# ADC.net
KiCad netlist of a schematic drawn in EAGLE
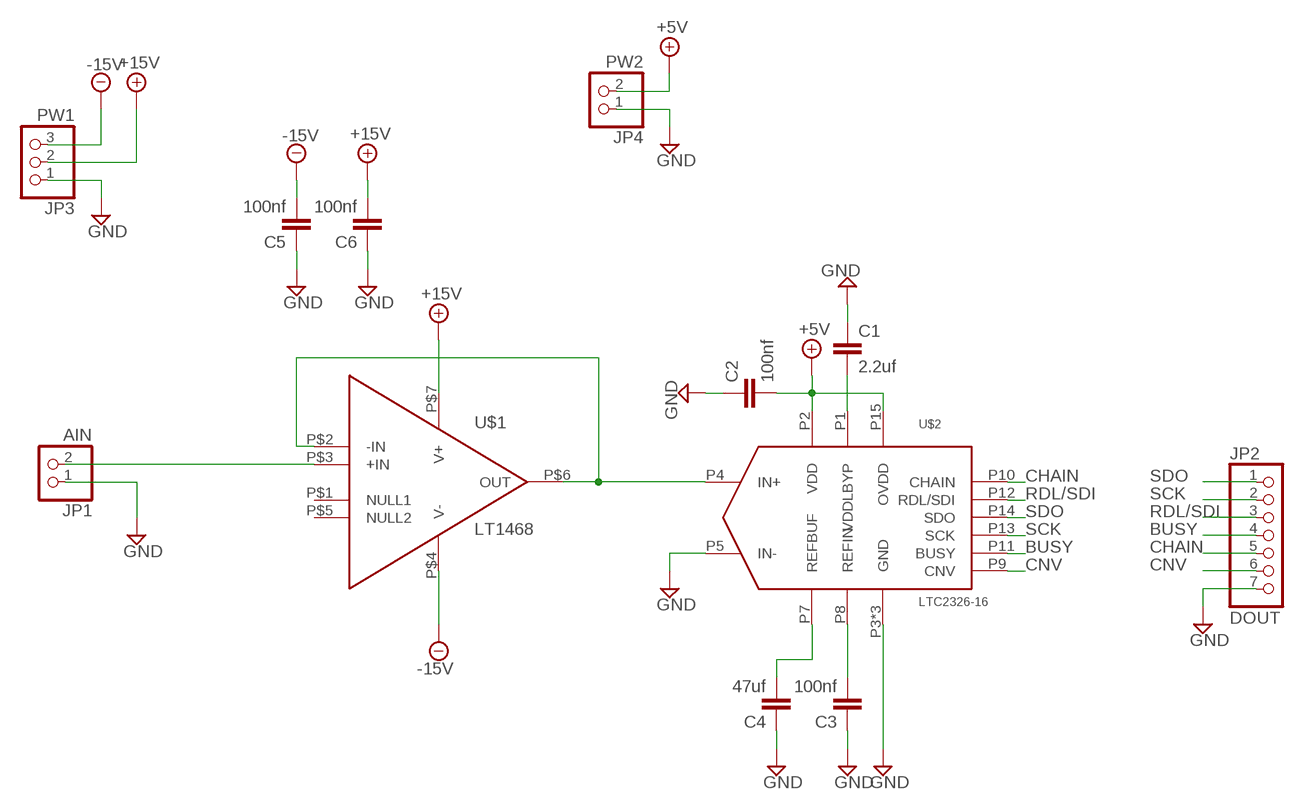
[diagram p0: schematic, sheet 1]

(export (version "E")
  (design (tool "Eeschema 10.0.6"))
  (components
    (comp (ref "C1")
      (value "2.2uf")
      (footprint "eagle-import:C0603")
      (libsource (lib "eagle-import") (part "C-EUC0603"))
    )
    (comp (ref "C2")
      (value "100nf")
      (footprint "eagle-import:C0603")
      (libsource (lib "eagle-import") (part "C-EUC0603"))
    )
    (comp (ref "C3")
      (value "100nf")
      (footprint "eagle-import:C0603")
      (libsource (lib "eagle-import") (part "C-EUC0603"))
    )
    (comp (ref "C4")
      (value "47uf")
      (footprint "eagle-import:C0603")
      (libsource (lib "eagle-import") (part "C-EUC0603"))
    )
    (comp (ref "C5")
      (value "100nf")
      (footprint "eagle-import:C0603")
      (libsource (lib "eagle-import") (part "C-EUC0603"))
    )
    (comp (ref "C6")
      (value "100nf")
      (footprint "eagle-import:C0603")
      (libsource (lib "eagle-import") (part "C-EUC0603"))
    )
    (comp (ref "JP1")
      (value "AIN")
      (footprint "eagle-import:1X02")
      (libsource (lib "eagle-import") (part "PINHD-1X2"))
    )
    (comp (ref "JP2")
      (value "DOUT")
      (footprint "eagle-import:1X07")
      (libsource (lib "eagle-import") (part "PINHD-1X7"))
    )
    (comp (ref "JP3")
      (value "PW1")
      (footprint "eagle-import:1X03")
      (libsource (lib "eagle-import") (part "PINHD-1X3"))
    )
    (comp (ref "JP4")
      (value "PW2")
      (footprint "eagle-import:1X02")
      (libsource (lib "eagle-import") (part "PINHD-1X2"))
    )
    (comp (ref "U$1")
      (value "LT1468")
      (footprint "eagle-import:SOIC-8")
      (libsource (lib "eagle-import") (part "LT1468"))
    )
    (comp (ref "U$2")
      (value "LTC2326-16")
      (footprint "eagle-import:16-MSOP")
      (libsource (lib "eagle-import") (part "LTC2326-16"))
    )
  )
  (nets
    (net (code "1") (name "+5V") (class "Default")
      (node (ref "C2") (pin "2") (pinfunction "2_2") (pintype "passive"))
      (node (ref "JP4") (pin "2") (pinfunction "2_2") (pintype "passive"))
      (node (ref "U$2") (pin "P15") (pinfunction "OVDD_P15") (pintype "bidirectional"))
      (node (ref "U$2") (pin "P2") (pinfunction "VDD_P2") (pintype "power_in"))
    )
    (net (code "2") (name "+15V") (class "Default")
      (node (ref "C6") (pin "2") (pinfunction "2_2") (pintype "passive"))
      (node (ref "JP3") (pin "2") (pinfunction "2_2") (pintype "passive"))
      (node (ref "U$1") (pin "P$7") (pinfunction "V+_P$7") (pintype "power_in"))
    )
    (net (code "3") (name "-15V") (class "Default")
      (node (ref "C5") (pin "2") (pinfunction "2_2") (pintype "passive"))
      (node (ref "JP3") (pin "3") (pinfunction "3_3") (pintype "passive"))
      (node (ref "U$1") (pin "P$4") (pinfunction "V-_P$4") (pintype "power_in"))
    )
    (net (code "4") (name "/BUSY") (class "Default")
      (node (ref "JP2") (pin "4") (pinfunction "4_4") (pintype "passive"))
      (node (ref "U$2") (pin "P11") (pinfunction "BUSY_P11") (pintype "output"))
    )
    (net (code "5") (name "/CHAIN") (class "Default")
      (node (ref "JP2") (pin "5") (pinfunction "5_5") (pintype "passive"))
      (node (ref "U$2") (pin "P10") (pinfunction "CHAIN_P10") (pintype "input"))
    )
    (net (code "6") (name "/CNV") (class "Default")
      (node (ref "JP2") (pin "6") (pinfunction "6_6") (pintype "passive"))
      (node (ref "U$2") (pin "P9") (pinfunction "CNV_P9") (pintype "input"))
    )
    (net (code "7") (name "/RDL{slash}SDI") (class "Default")
      (node (ref "JP2") (pin "3") (pinfunction "3_3") (pintype "passive"))
      (node (ref "U$2") (pin "P12") (pinfunction "RDL/SDI_P12") (pintype "input"))
    )
    (net (code "8") (name "/SCK") (class "Default")
      (node (ref "JP2") (pin "2") (pinfunction "2_2") (pintype "passive"))
      (node (ref "U$2") (pin "P13") (pinfunction "SCK_P13") (pintype "input"))
    )
    (net (code "9") (name "/SDO") (class "Default")
      (node (ref "JP2") (pin "1") (pinfunction "1_1") (pintype "passive"))
      (node (ref "U$2") (pin "P14") (pinfunction "SDO_P14") (pintype "output"))
    )
    (net (code "10") (name "GND") (class "Default")
      (node (ref "C1") (pin "1") (pinfunction "1_1") (pintype "passive"))
      (node (ref "C2") (pin "1") (pinfunction "1_1") (pintype "passive"))
      (node (ref "C3") (pin "1") (pinfunction "1_1") (pintype "passive"))
      (node (ref "C4") (pin "1") (pinfunction "1_1") (pintype "passive"))
      (node (ref "C5") (pin "1") (pinfunction "1_1") (pintype "passive"))
      (node (ref "C6") (pin "1") (pinfunction "1_1") (pintype "passive"))
      (node (ref "JP1") (pin "1") (pinfunction "1_1") (pintype "passive"))
      (node (ref "JP2") (pin "7") (pinfunction "7_7") (pintype "passive"))
      (node (ref "JP3") (pin "1") (pinfunction "1_1") (pintype "passive"))
      (node (ref "JP4") (pin "1") (pinfunction "1_1") (pintype "passive"))
      (node (ref "U$2") (pin "P16") (pinfunction "GND_P16") (pintype "power_in"))
      (node (ref "U$2") (pin "P3") (pinfunction "GND_P3") (pintype "power_in"))
      (node (ref "U$2") (pin "P5") (pinfunction "IN-_P5") (pintype "input"))
      (node (ref "U$2") (pin "P6") (pinfunction "GND_P6") (pintype "power_in"))
    )
    (net (code "11") (name "Net-(U$1-+IN)") (class "Default")
      (node (ref "JP1") (pin "2") (pinfunction "2_2") (pintype "passive"))
      (node (ref "U$1") (pin "P$3") (pinfunction "+IN_P$3") (pintype "input"))
    )
    (net (code "12") (name "Net-(U$1--IN)") (class "Default")
      (node (ref "U$1") (pin "P$2") (pinfunction "-IN_P$2") (pintype "input"))
      (node (ref "U$1") (pin "P$6") (pinfunction "OUT_P$6") (pintype "output"))
      (node (ref "U$2") (pin "P4") (pinfunction "IN+_P4") (pintype "input"))
    )
    (net (code "13") (name "Net-(U$2-REFBUF)") (class "Default")
      (node (ref "C4") (pin "2") (pinfunction "2_2") (pintype "passive"))
      (node (ref "U$2") (pin "P7") (pinfunction "REFBUF_P7") (pintype "bidirectional"))
    )
    (net (code "14") (name "Net-(U$2-REFIN)") (class "Default")
      (node (ref "C3") (pin "2") (pinfunction "2_2") (pintype "passive"))
      (node (ref "U$2") (pin "P8") (pinfunction "REFIN_P8") (pintype "bidirectional"))
    )
    (net (code "15") (name "Net-(U$2-VDDLBYP)") (class "Default")
      (node (ref "C1") (pin "2") (pinfunction "2_2") (pintype "passive"))
      (node (ref "U$2") (pin "P1") (pinfunction "VDDLBYP_P1") (pintype "output"))
    )
    (net (code "16") (name "unconnected-(U$1-NULL1-PadP$1)") (class "Default")
      (node (ref "U$1") (pin "P$1") (pinfunction "NULL1_P$1") (pintype "bidirectional"))
    )
    (net (code "17") (name "unconnected-(U$1-NULL2-PadP$5)") (class "Default")
      (node (ref "U$1") (pin "P$5") (pinfunction "NULL2_P$5") (pintype "bidirectional"))
    )
  )
)
